# Integrador.net
KiCad netlist of a schematic drawn in EAGLE
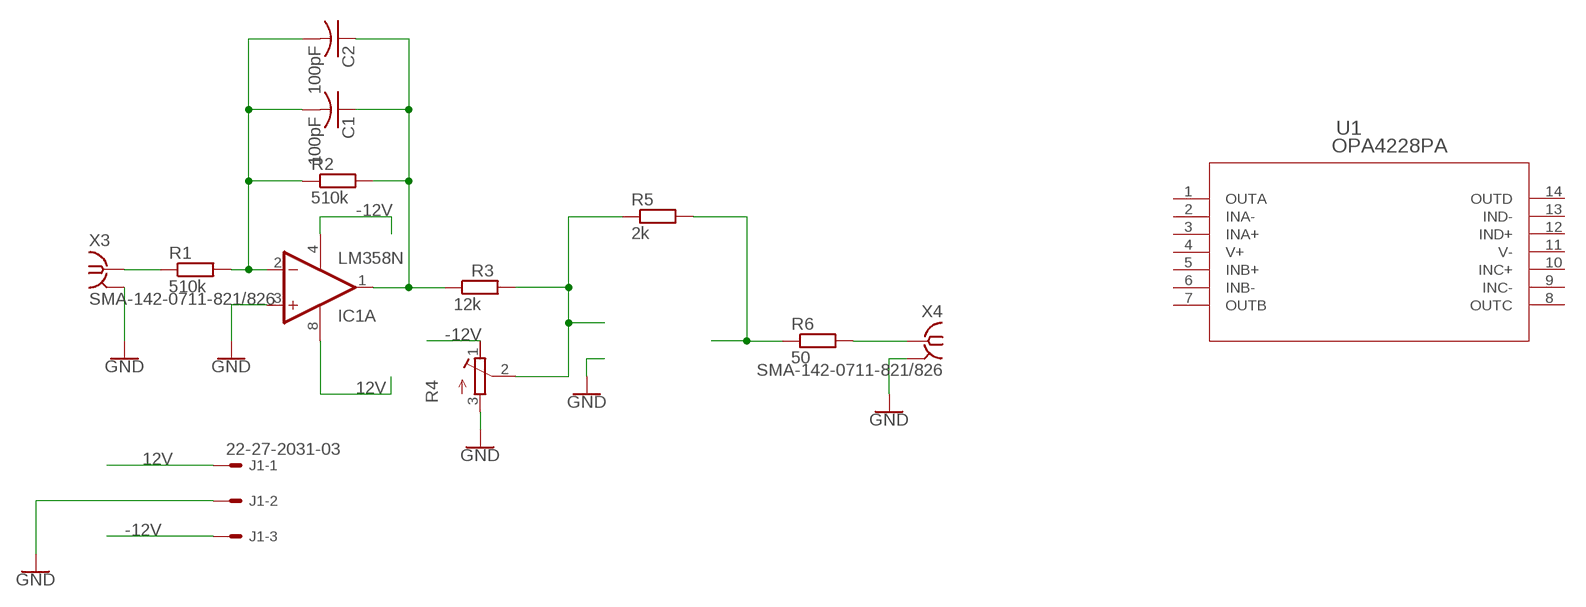
[diagram p0: schematic, sheet 1]

(export (version "E")
  (design (tool "Eeschema 10.0.6"))
  (components
    (comp (ref "C1")
      (value "100pF")
      (footprint "eagle-import:C025-030X050")
      (libsource (lib "eagle-import") (part "C-US025-030X050"))
    )
    (comp (ref "C2")
      (value "100pF")
      (footprint "eagle-import:C025-030X050")
      (libsource (lib "eagle-import") (part "C-US025-030X050"))
    )
    (comp (ref "IC1")
      (value "LM358N")
      (footprint "eagle-import:DIL08")
      (libsource (lib "eagle-import") (part "LM358N"))
    )
    (comp (ref "J1")
      (value "22-27-2031-03")
      (footprint "eagle-import:6410-03")
      (fields (field (name "MF") "MOLEX"))
      (libsource (lib "eagle-import") (part "22-?-0327-2031"))
    )
    (comp (ref "R1")
      (value "510k")
      (footprint "eagle-import:0207_10")
      (libsource (lib "eagle-import") (part "R-EU_0207/10"))
    )
    (comp (ref "R2")
      (value "510k")
      (footprint "eagle-import:0207_10")
      (libsource (lib "eagle-import") (part "R-EU_0207/10"))
    )
    (comp (ref "R3")
      (value "12k")
      (footprint "eagle-import:0207_10")
      (libsource (lib "eagle-import") (part "R-EU_0207/10"))
    )
    (comp (ref "R4")
      (value "R-TRIMM3006P")
      (footprint "eagle-import:RTRIM3006P")
      (libsource (lib "eagle-import") (part "R-TRIMM3006P"))
    )
    (comp (ref "R5")
      (value "2k")
      (footprint "eagle-import:0207_10")
      (libsource (lib "eagle-import") (part "R-EU_0207/10"))
    )
    (comp (ref "R6")
      (value "50")
      (footprint "eagle-import:0207_10")
      (libsource (lib "eagle-import") (part "R-EU_0207/10"))
    )
    (comp (ref "U1")
      (value "OPA4228PA")
      (footprint "eagle-import:N14")
      (fields
        (field (name "GENERIC_PART_NUMBER") "OPA4228")
        (field (name "MANUFACTURER") "Texas Instruments")
      )
      (libsource (lib "eagle-import") (part "OPA4228PA"))
    )
    (comp (ref "X3")
      (value "SMA-142-0711-821/826")
      (footprint "eagle-import:J502-ND-142-0711-821_826")
      (fields (field (name "MF") "JOHNSON COMPONENTS") (field (name "MPN") "142-0711-821"))
      (libsource (lib "eagle-import") (part "SMA-142-0711-821/826"))
    )
    (comp (ref "X4")
      (value "SMA-142-0711-821/826")
      (footprint "eagle-import:J502-ND-142-0711-821_826")
      (fields (field (name "MF") "JOHNSON COMPONENTS") (field (name "MPN") "142-0711-821"))
      (libsource (lib "eagle-import") (part "SMA-142-0711-821/826"))
    )
  )
  (nets
    (net (code "1") (name "/-12V") (class "Default")
      (node (ref "IC1") (pin "4") (pinfunction "V-_4") (pintype "power_in"))
      (node (ref "J1") (pin "3") (pinfunction "S_3") (pintype "passive"))
      (node (ref "R4") (pin "1") (pinfunction "E_1") (pintype "passive"))
    )
    (net (code "2") (name "/12V") (class "Default")
      (node (ref "IC1") (pin "8") (pinfunction "V+_8") (pintype "power_in"))
      (node (ref "J1") (pin "1") (pinfunction "S_1") (pintype "passive"))
    )
    (net (code "3") (name "/V+") (class "Default")
      (node (ref "U1") (pin "4") (pinfunction "V+_4") (pintype "power_in"))
    )
    (net (code "4") (name "/V-") (class "Default")
      (node (ref "U1") (pin "11") (pinfunction "V-_11") (pintype "power_in"))
    )
    (net (code "5") (name "GND") (class "Default")
      (node (ref "IC1") (pin "3") (pinfunction "+IN_3") (pintype "input"))
      (node (ref "J1") (pin "2") (pinfunction "S_2") (pintype "passive"))
      (node (ref "R4") (pin "3") (pinfunction "A_3") (pintype "passive"))
      (node (ref "X3") (pin "G@1") (pinfunction "2_G@1") (pintype "passive"))
      (node (ref "X3") (pin "G@2") (pinfunction "2_G@2") (pintype "passive"))
      (node (ref "X3") (pin "G@3") (pinfunction "2_G@3") (pintype "passive"))
      (node (ref "X3") (pin "G@4") (pinfunction "2_G@4") (pintype "passive"))
      (node (ref "X4") (pin "G@1") (pinfunction "2_G@1") (pintype "passive"))
      (node (ref "X4") (pin "G@2") (pinfunction "2_G@2") (pintype "passive"))
      (node (ref "X4") (pin "G@3") (pinfunction "2_G@3") (pintype "passive"))
      (node (ref "X4") (pin "G@4") (pinfunction "2_G@4") (pintype "passive"))
    )
    (net (code "6") (name "Net-(IC1A--IN)") (class "Default")
      (node (ref "C1") (pin "2") (pinfunction "2_2") (pintype "passive"))
      (node (ref "C2") (pin "2") (pinfunction "2_2") (pintype "passive"))
      (node (ref "IC1") (pin "2") (pinfunction "-IN_2") (pintype "input"))
      (node (ref "R1") (pin "2") (pinfunction "2_2") (pintype "passive"))
      (node (ref "R2") (pin "1") (pinfunction "1_1") (pintype "passive"))
    )
    (net (code "7") (name "Net-(IC1A-OUT)") (class "Default")
      (node (ref "C1") (pin "1") (pinfunction "1_1") (pintype "passive"))
      (node (ref "C2") (pin "1") (pinfunction "1_1") (pintype "passive"))
      (node (ref "IC1") (pin "1") (pinfunction "OUT_1") (pintype "output"))
      (node (ref "R2") (pin "2") (pinfunction "2_2") (pintype "passive"))
      (node (ref "R3") (pin "1") (pinfunction "1_1") (pintype "passive"))
    )
    (net (code "8") (name "Net-(R1-Pad1)") (class "Default")
      (node (ref "R1") (pin "1") (pinfunction "1_1") (pintype "passive"))
      (node (ref "X3") (pin "1") (pinfunction "1_1") (pintype "passive"))
    )
    (net (code "9") (name "Net-(R4-S)") (class "Default")
      (node (ref "R3") (pin "2") (pinfunction "2_2") (pintype "passive"))
      (node (ref "R4") (pin "2") (pinfunction "S_2") (pintype "passive"))
      (node (ref "R5") (pin "1") (pinfunction "1_1") (pintype "passive"))
    )
    (net (code "10") (name "Net-(R5-Pad2)") (class "Default")
      (node (ref "R5") (pin "2") (pinfunction "2_2") (pintype "passive"))
      (node (ref "R6") (pin "1") (pinfunction "1_1") (pintype "passive"))
    )
    (net (code "11") (name "Net-(R6-Pad2)") (class "Default")
      (node (ref "R6") (pin "2") (pinfunction "2_2") (pintype "passive"))
      (node (ref "X4") (pin "1") (pinfunction "1_1") (pintype "passive"))
    )
    (net (code "12") (name "unconnected-(U1-INA+-Pad3)") (class "Default")
      (node (ref "U1") (pin "3") (pinfunction "INA+_3") (pintype "input"))
    )
    (net (code "13") (name "unconnected-(U1-INA--Pad2)") (class "Default")
      (node (ref "U1") (pin "2") (pinfunction "INA-_2") (pintype "input"))
    )
    (net (code "14") (name "unconnected-(U1-INB+-Pad5)") (class "Default")
      (node (ref "U1") (pin "5") (pinfunction "INB+_5") (pintype "input"))
    )
    (net (code "15") (name "unconnected-(U1-INB--Pad6)") (class "Default")
      (node (ref "U1") (pin "6") (pinfunction "INB-_6") (pintype "input"))
    )
    (net (code "16") (name "unconnected-(U1-INC+-Pad10)") (class "Default")
      (node (ref "U1") (pin "10") (pinfunction "INC+_10") (pintype "input"))
    )
    (net (code "17") (name "unconnected-(U1-INC--Pad9)") (class "Default")
      (node (ref "U1") (pin "9") (pinfunction "INC-_9") (pintype "input"))
    )
    (net (code "18") (name "unconnected-(U1-IND+-Pad12)") (class "Default")
      (node (ref "U1") (pin "12") (pinfunction "IND+_12") (pintype "input"))
    )
    (net (code "19") (name "unconnected-(U1-IND--Pad13)") (class "Default")
      (node (ref "U1") (pin "13") (pinfunction "IND-_13") (pintype "input"))
    )
    (net (code "20") (name "unconnected-(U1-OUTA-Pad1)") (class "Default")
      (node (ref "U1") (pin "1") (pinfunction "OUTA_1") (pintype "output"))
    )
    (net (code "21") (name "unconnected-(U1-OUTB-Pad7)") (class "Default")
      (node (ref "U1") (pin "7") (pinfunction "OUTB_7") (pintype "output"))
    )
    (net (code "22") (name "unconnected-(U1-OUTC-Pad8)") (class "Default")
      (node (ref "U1") (pin "8") (pinfunction "OUTC_8") (pintype "output"))
    )
    (net (code "23") (name "unconnected-(U1-OUTD-Pad14)") (class "Default")
      (node (ref "U1") (pin "14") (pinfunction "OUTD_14") (pintype "output"))
    )
  )
)
